# gc1.net
KiCad netlist of a schematic drawn in EAGLE
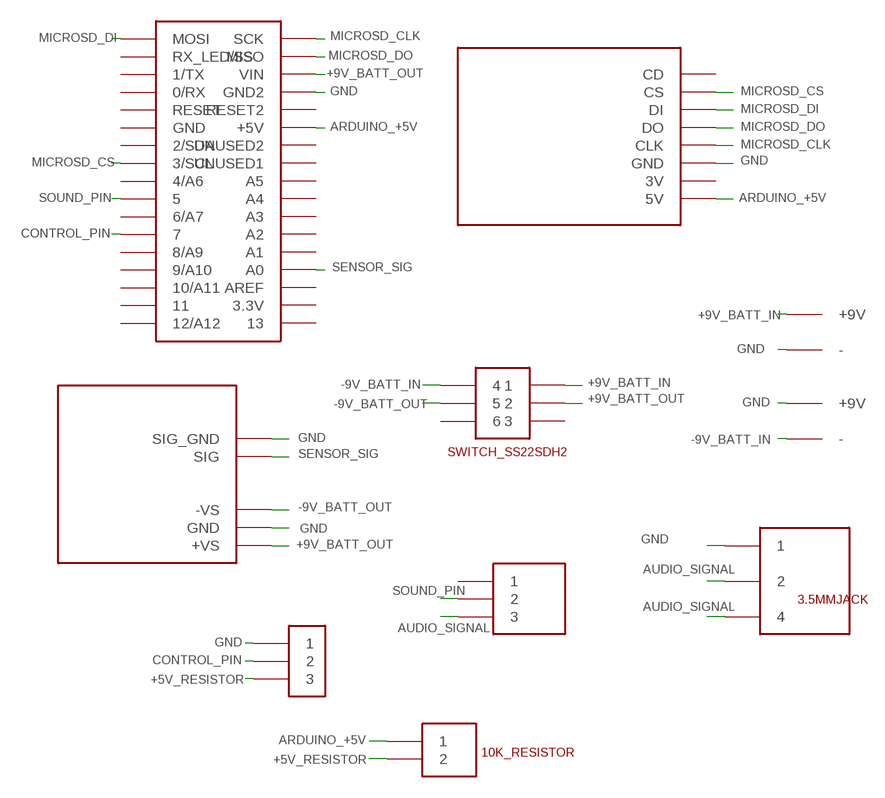
[diagram p0: schematic, sheet 1]

(export (version "E")
  (design (tool "Eeschema 10.0.6"))
  (components
    (comp (ref "3.5MMJACK")
      (value "35RAPC2BVN4")
      (footprint "eagle-import:35RAPC4BVN4")
      (libsource (lib "eagle-import") (part "35RAPC2BVN4"))
    )
    (comp (ref "10K_RESISTOR")
      (value "10K_RESISTOR")
      (footprint "eagle-import:10K_RESISTOR")
      (libsource (lib "eagle-import") (part "10K_RESISTOR"))
    )
    (comp (ref "ARDUINOMICRO")
      (value "ARDUINO_MICRO")
      (footprint "eagle-import:ARDUINO_MICRO")
      (libsource (lib "eagle-import") (part "ARDUINO_MICRO"))
    )
    (comp (ref "TRIMMER")
      (value "66WR1KLF")
      (footprint "eagle-import:66WR1KLF")
      (libsource (lib "eagle-import") (part "66WR1KLF"))
    )
    (comp (ref "U$2")
      (value "MICROSD")
      (footprint "eagle-import:MICROSD")
      (libsource (lib "eagle-import") (part "MICROSD"))
    )
    (comp (ref "U$3")
      (value "MUSCLE_SENSOR")
      (footprint "eagle-import:MUSCLE_SENSOR")
      (libsource (lib "eagle-import") (part "MUSCLE_SENSOR"))
    )
    (comp (ref "U$4")
      (value "SWITCH_SS22SDH2")
      (footprint "eagle-import:SWITCH_SS22SDH2")
      (libsource (lib "eagle-import") (part "SWITCH_SS22SDH2"))
    )
    (comp (ref "U$5")
      (value "9V_CONNECTOR")
      (footprint "eagle-import:9V_CONNECTOR")
      (libsource (lib "eagle-import") (part "9V_CONNECTOR"))
    )
    (comp (ref "U$6")
      (value "9V_CONNECTOR")
      (footprint "eagle-import:9V_CONNECTOR")
      (libsource (lib "eagle-import") (part "9V_CONNECTOR"))
    )
    (comp (ref "U$9")
      (value "SWITCH_SS12SDH2")
      (footprint "eagle-import:SWITCH_SS12SDH2")
      (libsource (lib "eagle-import") (part "SWITCH_SS12SDH2"))
    )
  )
  (nets
    (net (code "1") (name "/+5V_RESISTOR") (class "Default")
      (node (ref "10K_RESISTOR") (pin "2") (pinfunction "2_2") (pintype "bidirectional"))
      (node (ref "U$9") (pin "3") (pinfunction "3_3") (pintype "bidirectional"))
    )
    (net (code "2") (name "/+9V_BATT_IN") (class "Default")
      (node (ref "U$4") (pin "1") (pinfunction "1_1") (pintype "bidirectional"))
      (node (ref "U$5") (pin "+9V") (pinfunction "+9V_+9V") (pintype "bidirectional"))
    )
    (net (code "3") (name "/+9V_BATT_OUT") (class "Default")
      (node (ref "ARDUINOMICRO") (pin "VIN") (pinfunction "VIN_VIN") (pintype "bidirectional"))
      (node (ref "U$3") (pin "+VS") (pinfunction "+VS_+VS") (pintype "bidirectional"))
      (node (ref "U$4") (pin "2") (pinfunction "2_2") (pintype "bidirectional"))
    )
    (net (code "4") (name "/-9V_BATT_IN") (class "Default")
      (node (ref "U$4") (pin "4") (pinfunction "4_4") (pintype "bidirectional"))
      (node (ref "U$6") (pin "-") (pinfunction "-_-") (pintype "bidirectional"))
    )
    (net (code "5") (name "/-9V_BATT_OUT") (class "Default")
      (node (ref "U$3") (pin "-VS") (pinfunction "-VS_-VS") (pintype "bidirectional"))
      (node (ref "U$4") (pin "5") (pinfunction "5_5") (pintype "bidirectional"))
    )
    (net (code "6") (name "/ARDUINO_+5V") (class "Default")
      (node (ref "10K_RESISTOR") (pin "1") (pinfunction "1_1") (pintype "bidirectional"))
      (node (ref "ARDUINOMICRO") (pin "+5V") (pinfunction "+5V_+5V") (pintype "bidirectional"))
      (node (ref "U$2") (pin "5V") (pinfunction "5V_5V") (pintype "bidirectional"))
    )
    (net (code "7") (name "/AUDIO_SIGNAL") (class "Default")
      (node (ref "3.5MMJACK") (pin "2") (pinfunction "2_2") (pintype "bidirectional"))
      (node (ref "3.5MMJACK") (pin "4") (pinfunction "4_4") (pintype "bidirectional"))
      (node (ref "TRIMMER") (pin "3") (pinfunction "3_3") (pintype "bidirectional"))
    )
    (net (code "8") (name "/CONTROL_PIN") (class "Default")
      (node (ref "ARDUINOMICRO") (pin "7") (pinfunction "7_7") (pintype "bidirectional"))
      (node (ref "U$9") (pin "2") (pinfunction "2_2") (pintype "bidirectional"))
    )
    (net (code "9") (name "/GND") (class "Default")
      (node (ref "3.5MMJACK") (pin "1") (pinfunction "1_1") (pintype "bidirectional"))
      (node (ref "ARDUINOMICRO") (pin "GND2") (pinfunction "GND2_GND2") (pintype "bidirectional"))
      (node (ref "U$2") (pin "GND") (pinfunction "GND_GND") (pintype "bidirectional"))
      (node (ref "U$3") (pin "GND") (pinfunction "GND_GND") (pintype "bidirectional"))
      (node (ref "U$3") (pin "SIG_GND") (pinfunction "SIG_GND_SIG_GND") (pintype "bidirectional"))
      (node (ref "U$5") (pin "-") (pinfunction "-_-") (pintype "bidirectional"))
      (node (ref "U$6") (pin "+9V") (pinfunction "+9V_+9V") (pintype "bidirectional"))
      (node (ref "U$9") (pin "1") (pinfunction "1_1") (pintype "bidirectional"))
    )
    (net (code "10") (name "/MICROSD_CLK") (class "Default")
      (node (ref "ARDUINOMICRO") (pin "SCK") (pinfunction "SCK_SCK") (pintype "bidirectional"))
      (node (ref "U$2") (pin "CLK") (pinfunction "CLK_CLK") (pintype "bidirectional"))
    )
    (net (code "11") (name "/MICROSD_CS") (class "Default")
      (node (ref "ARDUINOMICRO") (pin "3/SCL") (pinfunction "3/SCL_3/SCL") (pintype "bidirectional"))
      (node (ref "U$2") (pin "CS") (pinfunction "CS_CS") (pintype "bidirectional"))
    )
    (net (code "12") (name "/MICROSD_DI") (class "Default")
      (node (ref "ARDUINOMICRO") (pin "MOSI") (pinfunction "MOSI_MOSI") (pintype "bidirectional"))
      (node (ref "U$2") (pin "DI") (pinfunction "DI_DI") (pintype "bidirectional"))
    )
    (net (code "13") (name "/MICROSD_DO") (class "Default")
      (node (ref "ARDUINOMICRO") (pin "MISO") (pinfunction "MISO_MISO") (pintype "bidirectional"))
      (node (ref "U$2") (pin "DO") (pinfunction "DO_DO") (pintype "bidirectional"))
    )
    (net (code "14") (name "/SENSOR_SIG") (class "Default")
      (node (ref "ARDUINOMICRO") (pin "A0") (pinfunction "A0_A0") (pintype "bidirectional"))
      (node (ref "U$3") (pin "SIG") (pinfunction "SIG_SIG") (pintype "bidirectional"))
    )
    (net (code "15") (name "/SOUND_PIN") (class "Default")
      (node (ref "ARDUINOMICRO") (pin "5") (pinfunction "5_5") (pintype "bidirectional"))
      (node (ref "TRIMMER") (pin "2") (pinfunction "2_2") (pintype "bidirectional"))
    )
    (net (code "16") (name "unconnected-(ARDUINOMICRO-Pad0{slash}RX)") (class "Default")
      (node (ref "ARDUINOMICRO") (pin "0/RX") (pinfunction "0/RX_0/RX") (pintype "bidirectional"))
    )
    (net (code "17") (name "unconnected-(ARDUINOMICRO-Pad1{slash}TX)") (class "Default")
      (node (ref "ARDUINOMICRO") (pin "1/TX") (pinfunction "1/TX_1/TX") (pintype "bidirectional"))
    )
    (net (code "18") (name "unconnected-(ARDUINOMICRO-Pad2{slash}SDA)") (class "Default")
      (node (ref "ARDUINOMICRO") (pin "2/SDA") (pinfunction "2/SDA_2/SDA") (pintype "bidirectional"))
    )
    (net (code "19") (name "unconnected-(ARDUINOMICRO-Pad3.3V)") (class "Default")
      (node (ref "ARDUINOMICRO") (pin "3.3V") (pinfunction "3.3V_3.3V") (pintype "bidirectional"))
    )
    (net (code "20") (name "unconnected-(ARDUINOMICRO-Pad4{slash}A6)") (class "Default")
      (node (ref "ARDUINOMICRO") (pin "4/A6") (pinfunction "4/A6_4/A6") (pintype "bidirectional"))
    )
    (net (code "21") (name "unconnected-(ARDUINOMICRO-Pad6{slash}A7)") (class "Default")
      (node (ref "ARDUINOMICRO") (pin "6/A7") (pinfunction "6/A7_6/A7") (pintype "bidirectional"))
    )
    (net (code "22") (name "unconnected-(ARDUINOMICRO-Pad8{slash}A9)") (class "Default")
      (node (ref "ARDUINOMICRO") (pin "8/A9") (pinfunction "8/A9_8/A9") (pintype "bidirectional"))
    )
    (net (code "23") (name "unconnected-(ARDUINOMICRO-Pad9{slash}A10)") (class "Default")
      (node (ref "ARDUINOMICRO") (pin "9/A10") (pinfunction "9/A10_9/A10") (pintype "bidirectional"))
    )
    (net (code "24") (name "unconnected-(ARDUINOMICRO-Pad10{slash}A11)") (class "Default")
      (node (ref "ARDUINOMICRO") (pin "10/A11") (pinfunction "10/A11_10/A11") (pintype "bidirectional"))
    )
    (net (code "25") (name "unconnected-(ARDUINOMICRO-Pad11)") (class "Default")
      (node (ref "ARDUINOMICRO") (pin "11") (pinfunction "11_11") (pintype "bidirectional"))
    )
    (net (code "26") (name "unconnected-(ARDUINOMICRO-Pad12{slash}A12)") (class "Default")
      (node (ref "ARDUINOMICRO") (pin "12/A12") (pinfunction "12/A12_12/A12") (pintype "bidirectional"))
    )
    (net (code "27") (name "unconnected-(ARDUINOMICRO-Pad13)") (class "Default")
      (node (ref "ARDUINOMICRO") (pin "13") (pinfunction "13_13") (pintype "bidirectional"))
    )
    (net (code "28") (name "unconnected-(ARDUINOMICRO-PadA1)") (class "Default")
      (node (ref "ARDUINOMICRO") (pin "A1") (pinfunction "A1_A1") (pintype "bidirectional"))
    )
    (net (code "29") (name "unconnected-(ARDUINOMICRO-PadA2)") (class "Default")
      (node (ref "ARDUINOMICRO") (pin "A2") (pinfunction "A2_A2") (pintype "bidirectional"))
    )
    (net (code "30") (name "unconnected-(ARDUINOMICRO-PadA3)") (class "Default")
      (node (ref "ARDUINOMICRO") (pin "A3") (pinfunction "A3_A3") (pintype "bidirectional"))
    )
    (net (code "31") (name "unconnected-(ARDUINOMICRO-PadA4)") (class "Default")
      (node (ref "ARDUINOMICRO") (pin "A4") (pinfunction "A4_A4") (pintype "bidirectional"))
    )
    (net (code "32") (name "unconnected-(ARDUINOMICRO-PadA5)") (class "Default")
      (node (ref "ARDUINOMICRO") (pin "A5") (pinfunction "A5_A5") (pintype "bidirectional"))
    )
    (net (code "33") (name "unconnected-(ARDUINOMICRO-PadAREF)") (class "Default")
      (node (ref "ARDUINOMICRO") (pin "AREF") (pinfunction "AREF_AREF") (pintype "bidirectional"))
    )
    (net (code "34") (name "unconnected-(ARDUINOMICRO-PadGND)") (class "Default")
      (node (ref "ARDUINOMICRO") (pin "GND") (pinfunction "GND_GND") (pintype "bidirectional"))
    )
    (net (code "35") (name "unconnected-(ARDUINOMICRO-PadRESET)") (class "Default")
      (node (ref "ARDUINOMICRO") (pin "RESET") (pinfunction "RESET_RESET") (pintype "bidirectional"))
    )
    (net (code "36") (name "unconnected-(ARDUINOMICRO-PadRESET2)") (class "Default")
      (node (ref "ARDUINOMICRO") (pin "RESET2") (pinfunction "RESET2_RESET2") (pintype "bidirectional"))
    )
    (net (code "37") (name "unconnected-(ARDUINOMICRO-PadRX_LED{slash}SS)") (class "Default")
      (node (ref "ARDUINOMICRO") (pin "RX_LED/SS") (pinfunction "RX_LED/SS_RX_LED/SS") (pintype "bidirectional"))
    )
    (net (code "38") (name "unconnected-(ARDUINOMICRO-PadUNUSED1)") (class "Default")
      (node (ref "ARDUINOMICRO") (pin "UNUSED1") (pinfunction "UNUSED1_UNUSED1") (pintype "bidirectional"))
    )
    (net (code "39") (name "unconnected-(ARDUINOMICRO-PadUNUSED2)") (class "Default")
      (node (ref "ARDUINOMICRO") (pin "UNUSED2") (pinfunction "UNUSED2_UNUSED2") (pintype "bidirectional"))
    )
    (net (code "40") (name "unconnected-(TRIMMER-Pad1)") (class "Default")
      (node (ref "TRIMMER") (pin "1") (pinfunction "1_1") (pintype "bidirectional"))
    )
    (net (code "41") (name "unconnected-(U$2-Pad3V)") (class "Default")
      (node (ref "U$2") (pin "3V") (pinfunction "3V_3V") (pintype "bidirectional"))
    )
    (net (code "42") (name "unconnected-(U$2-PadCD)") (class "Default")
      (node (ref "U$2") (pin "CD") (pinfunction "CD_CD") (pintype "bidirectional"))
    )
    (net (code "43") (name "unconnected-(U$4-Pad3)") (class "Default")
      (node (ref "U$4") (pin "3") (pinfunction "3_3") (pintype "bidirectional"))
    )
    (net (code "44") (name "unconnected-(U$4-Pad6)") (class "Default")
      (node (ref "U$4") (pin "6") (pinfunction "6_6") (pintype "bidirectional"))
    )
  )
)
